# naomi_io.net
KiCad netlist of a schematic drawn in EAGLE
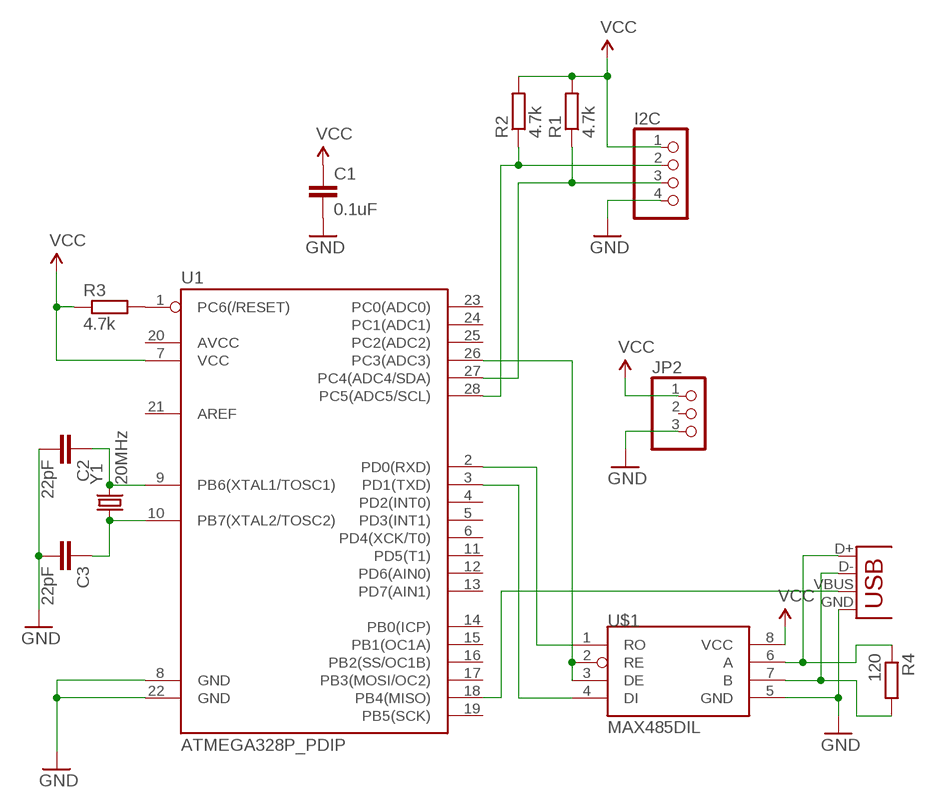
[diagram p0: schematic, sheet 1]

(export (version "E")
  (design (tool "Eeschema 10.0.6"))
  (components
    (comp (ref "C1")
      (value "0.1uF")
      (footprint "eagle-import:C025-030X050")
      (libsource (lib "eagle-import") (part "C-EU025-030X050"))
    )
    (comp (ref "C2")
      (value "22pF")
      (footprint "eagle-import:C025-030X050")
      (libsource (lib "eagle-import") (part "C-EU025-030X050"))
    )
    (comp (ref "C3")
      (value "22pF")
      (footprint "eagle-import:C025-030X050")
      (libsource (lib "eagle-import") (part "C-EU025-030X050"))
    )
    (comp (ref "I2C")
      (value "PINHD-1X4/90")
      (footprint "eagle-import:1X04_90")
      (libsource (lib "eagle-import") (part "PINHD-1X4/90"))
    )
    (comp (ref "JP1")
      (value "USB-B")
      (footprint "eagle-import:USB-B-PTH")
      (libsource (lib "eagle-import") (part "USBPTH"))
    )
    (comp (ref "JP2")
      (value "PINHD-1X3")
      (footprint "eagle-import:1X03")
      (libsource (lib "eagle-import") (part "PINHD-1X3"))
    )
    (comp (ref "R1")
      (value "4.7k")
      (footprint "eagle-import:0204_5")
      (libsource (lib "eagle-import") (part "R-EU_0204/5"))
    )
    (comp (ref "R2")
      (value "4.7k")
      (footprint "eagle-import:0204_5")
      (libsource (lib "eagle-import") (part "R-EU_0204/5"))
    )
    (comp (ref "R3")
      (value "4.7k")
      (footprint "eagle-import:0204_5")
      (libsource (lib "eagle-import") (part "R-EU_0204/5"))
    )
    (comp (ref "R4")
      (value "120")
      (footprint "eagle-import:0204_5")
      (libsource (lib "eagle-import") (part "R-EU_0204/5"))
    )
    (comp (ref "U$1")
      (value "MAX485DIL")
      (footprint "eagle-import:DIL08")
      (libsource (lib "eagle-import") (part "MAX485DIL"))
    )
    (comp (ref "U1")
      (value "ATMEGA328P_PDIP")
      (footprint "eagle-import:DIL28-3")
      (libsource (lib "eagle-import") (part "ATMEGA328P_PDIP"))
    )
    (comp (ref "Y1")
      (value "20MHz")
      (footprint "eagle-import:HC49US")
      (libsource (lib "eagle-import") (part "CRYSTALHC49US"))
    )
  )
  (nets
    (net (code "1") (name "GND") (class "Default")
      (node (ref "C1") (pin "2") (pinfunction "2_2") (pintype "passive"))
      (node (ref "C2") (pin "2") (pinfunction "2_2") (pintype "passive"))
      (node (ref "C3") (pin "2") (pinfunction "2_2") (pintype "passive"))
      (node (ref "I2C") (pin "4") (pinfunction "4_4") (pintype "passive"))
      (node (ref "JP1") (pin "GND") (pinfunction "GND_GND") (pintype "bidirectional"))
      (node (ref "JP2") (pin "3") (pinfunction "3_3") (pintype "passive"))
      (node (ref "U$1") (pin "5") (pinfunction "GND_5") (pintype "bidirectional"))
      (node (ref "U1") (pin "22") (pinfunction "GND_22") (pintype "bidirectional"))
      (node (ref "U1") (pin "8") (pinfunction "GND_8") (pintype "bidirectional"))
    )
    (net (code "2") (name "Net-(U$1-A)") (class "Default")
      (node (ref "JP1") (pin "D+") (pinfunction "D+_D+") (pintype "bidirectional"))
      (node (ref "R4") (pin "1") (pinfunction "1_1") (pintype "passive"))
      (node (ref "U$1") (pin "6") (pinfunction "A_6") (pintype "bidirectional"))
    )
    (net (code "3") (name "Net-(U$1-B)") (class "Default")
      (node (ref "JP1") (pin "D-") (pinfunction "D-_D-") (pintype "bidirectional"))
      (node (ref "R4") (pin "2") (pinfunction "2_2") (pintype "passive"))
      (node (ref "U$1") (pin "7") (pinfunction "B_7") (pintype "bidirectional"))
    )
    (net (code "4") (name "Net-(U$1-DE)") (class "Default")
      (node (ref "U$1") (pin "2") (pinfunction "RE_2") (pintype "bidirectional"))
      (node (ref "U$1") (pin "3") (pinfunction "DE_3") (pintype "bidirectional"))
      (node (ref "U1") (pin "26") (pinfunction "PC3(ADC3)_26") (pintype "bidirectional"))
    )
    (net (code "5") (name "Net-(U$1-DI)") (class "Default")
      (node (ref "U$1") (pin "4") (pinfunction "DI_4") (pintype "bidirectional"))
      (node (ref "U1") (pin "3") (pinfunction "PD1(TXD)_3") (pintype "bidirectional"))
    )
    (net (code "6") (name "Net-(U$1-RO)") (class "Default")
      (node (ref "U$1") (pin "1") (pinfunction "RO_1") (pintype "bidirectional"))
      (node (ref "U1") (pin "2") (pinfunction "PD0(RXD)_2") (pintype "bidirectional"))
    )
    (net (code "7") (name "Net-(U1-PB4(MISO))") (class "Default")
      (node (ref "JP1") (pin "VBUS") (pinfunction "VBUS_VBUS") (pintype "bidirectional"))
      (node (ref "U1") (pin "18") (pinfunction "PB4(MISO)_18") (pintype "bidirectional"))
    )
    (net (code "8") (name "Net-(U1-PB6(XTAL1{slash}TOSC1))") (class "Default")
      (node (ref "C2") (pin "1") (pinfunction "1_1") (pintype "passive"))
      (node (ref "U1") (pin "9") (pinfunction "PB6(XTAL1/TOSC1)_9") (pintype "bidirectional"))
      (node (ref "Y1") (pin "2") (pinfunction "2_2") (pintype "passive"))
    )
    (net (code "9") (name "Net-(U1-PB7(XTAL2{slash}TOSC2))") (class "Default")
      (node (ref "C3") (pin "1") (pinfunction "1_1") (pintype "passive"))
      (node (ref "U1") (pin "10") (pinfunction "PB7(XTAL2/TOSC2)_10") (pintype "bidirectional"))
      (node (ref "Y1") (pin "1") (pinfunction "1_1") (pintype "passive"))
    )
    (net (code "10") (name "Net-(U1-PC4(ADC4{slash}SDA))") (class "Default")
      (node (ref "I2C") (pin "3") (pinfunction "3_3") (pintype "passive"))
      (node (ref "R1") (pin "1") (pinfunction "1_1") (pintype "passive"))
      (node (ref "U1") (pin "27") (pinfunction "PC4(ADC4/SDA)_27") (pintype "bidirectional"))
    )
    (net (code "11") (name "Net-(U1-PC5(ADC5{slash}SCL))") (class "Default")
      (node (ref "I2C") (pin "2") (pinfunction "2_2") (pintype "passive"))
      (node (ref "R2") (pin "1") (pinfunction "1_1") (pintype "passive"))
      (node (ref "U1") (pin "28") (pinfunction "PC5(ADC5/SCL)_28") (pintype "bidirectional"))
    )
    (net (code "12") (name "Net-(U1-PC6({slash}RESET))") (class "Default")
      (node (ref "R3") (pin "2") (pinfunction "2_2") (pintype "passive"))
      (node (ref "U1") (pin "1") (pinfunction "PC6(/RESET)_1") (pintype "bidirectional"))
    )
    (net (code "13") (name "VCC") (class "Default")
      (node (ref "C1") (pin "1") (pinfunction "1_1") (pintype "passive"))
      (node (ref "I2C") (pin "1") (pinfunction "1_1") (pintype "passive"))
      (node (ref "JP2") (pin "1") (pinfunction "1_1") (pintype "passive"))
      (node (ref "R1") (pin "2") (pinfunction "2_2") (pintype "passive"))
      (node (ref "R2") (pin "2") (pinfunction "2_2") (pintype "passive"))
      (node (ref "R3") (pin "1") (pinfunction "1_1") (pintype "passive"))
      (node (ref "U$1") (pin "8") (pinfunction "VCC_8") (pintype "bidirectional"))
      (node (ref "U1") (pin "7") (pinfunction "VCC_7") (pintype "bidirectional"))
    )
    (net (code "14") (name "unconnected-(JP2-Pad2)") (class "Default")
      (node (ref "JP2") (pin "2") (pinfunction "2_2") (pintype "passive"))
    )
    (net (code "15") (name "unconnected-(U1-AREF-Pad21)") (class "Default")
      (node (ref "U1") (pin "21") (pinfunction "AREF_21") (pintype "bidirectional"))
    )
    (net (code "16") (name "unconnected-(U1-AVCC-Pad20)") (class "Default")
      (node (ref "U1") (pin "20") (pinfunction "AVCC_20") (pintype "bidirectional"))
    )
    (net (code "17") (name "unconnected-(U1-PB0(ICP)-Pad14)") (class "Default")
      (node (ref "U1") (pin "14") (pinfunction "PB0(ICP)_14") (pintype "bidirectional"))
    )
    (net (code "18") (name "unconnected-(U1-PB1(OC1A)-Pad15)") (class "Default")
      (node (ref "U1") (pin "15") (pinfunction "PB1(OC1A)_15") (pintype "bidirectional"))
    )
    (net (code "19") (name "unconnected-(U1-PB2(SS{slash}OC1B)-Pad16)") (class "Default")
      (node (ref "U1") (pin "16") (pinfunction "PB2(SS/OC1B)_16") (pintype "bidirectional"))
    )
    (net (code "20") (name "unconnected-(U1-PB3(MOSI{slash}OC2)-Pad17)") (class "Default")
      (node (ref "U1") (pin "17") (pinfunction "PB3(MOSI/OC2)_17") (pintype "bidirectional"))
    )
    (net (code "21") (name "unconnected-(U1-PB5(SCK)-Pad19)") (class "Default")
      (node (ref "U1") (pin "19") (pinfunction "PB5(SCK)_19") (pintype "bidirectional"))
    )
    (net (code "22") (name "unconnected-(U1-PC0(ADC0)-Pad23)") (class "Default")
      (node (ref "U1") (pin "23") (pinfunction "PC0(ADC0)_23") (pintype "bidirectional"))
    )
    (net (code "23") (name "unconnected-(U1-PC1(ADC1)-Pad24)") (class "Default")
      (node (ref "U1") (pin "24") (pinfunction "PC1(ADC1)_24") (pintype "bidirectional"))
    )
    (net (code "24") (name "unconnected-(U1-PC2(ADC2)-Pad25)") (class "Default")
      (node (ref "U1") (pin "25") (pinfunction "PC2(ADC2)_25") (pintype "bidirectional"))
    )
    (net (code "25") (name "unconnected-(U1-PD2(INT0)-Pad4)") (class "Default")
      (node (ref "U1") (pin "4") (pinfunction "PD2(INT0)_4") (pintype "bidirectional"))
    )
    (net (code "26") (name "unconnected-(U1-PD3(INT1)-Pad5)") (class "Default")
      (node (ref "U1") (pin "5") (pinfunction "PD3(INT1)_5") (pintype "bidirectional"))
    )
    (net (code "27") (name "unconnected-(U1-PD4(XCK{slash}T0)-Pad6)") (class "Default")
      (node (ref "U1") (pin "6") (pinfunction "PD4(XCK/T0)_6") (pintype "bidirectional"))
    )
    (net (code "28") (name "unconnected-(U1-PD5(T1)-Pad11)") (class "Default")
      (node (ref "U1") (pin "11") (pinfunction "PD5(T1)_11") (pintype "bidirectional"))
    )
    (net (code "29") (name "unconnected-(U1-PD6(AIN0)-Pad12)") (class "Default")
      (node (ref "U1") (pin "12") (pinfunction "PD6(AIN0)_12") (pintype "bidirectional"))
    )
    (net (code "30") (name "unconnected-(U1-PD7(AIN1)-Pad13)") (class "Default")
      (node (ref "U1") (pin "13") (pinfunction "PD7(AIN1)_13") (pintype "bidirectional"))
    )
  )
)
